# Manas_JLCPCB_2020-11-11_10-35-08.net
KiCad netlist of a schematic drawn in EasyEDA
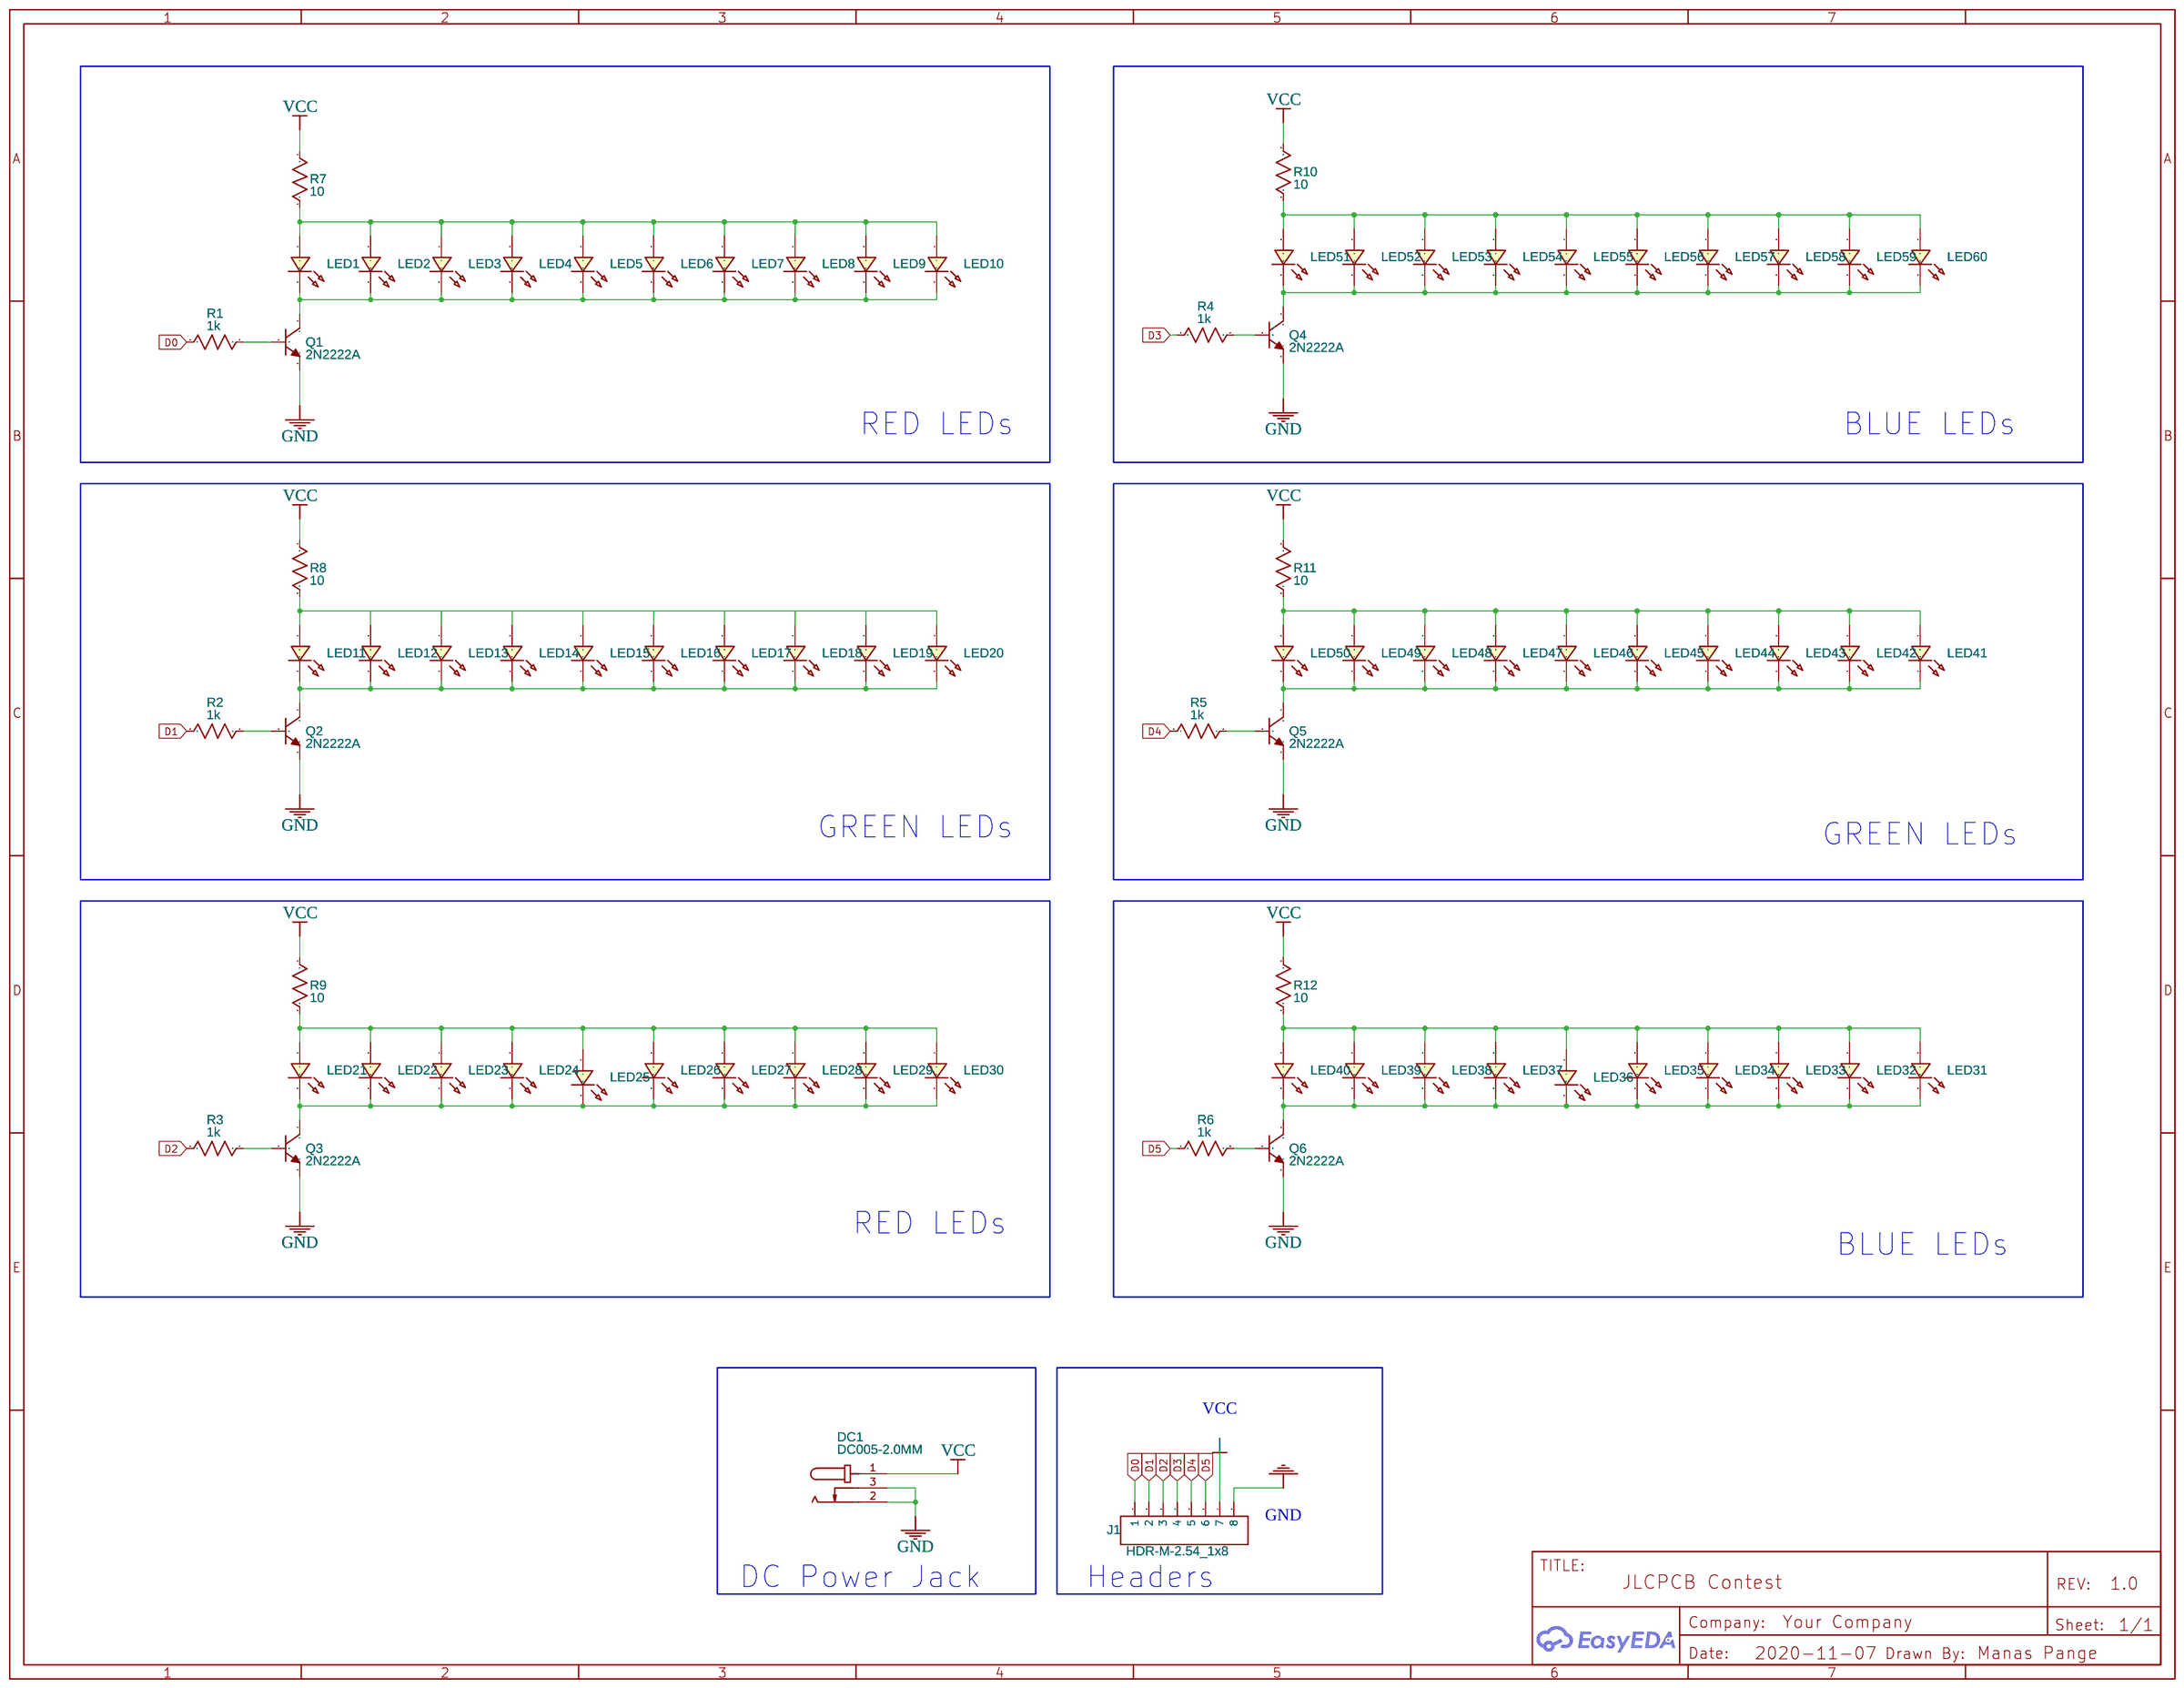
[diagram p0: schematic sheet]

(export (version "E")
  (design (tool "Eeschema 10.0.6"))
  (components
    (comp (ref "DC1")
      (value "DC005-2.0MM")
      (fields (field (name "BOM_Supplier Part") "C111567"))
      (libsource (lib "") (part "DC005-2.0MM"))
    )
    (comp (ref "J1")
      (value "HDR-M-2.54_1x8")
      (fields (field (name "BOM_Supplier Part") "C190820"))
      (libsource (lib "") (part "HDR-M-2.54_1x8"))
    )
    (comp (ref "LED1")
      (value "LED-TH-3mm_R")
      (fields
        (field (name "BOM_Manufacturer Part") "204-10SDRD/S530-A3-L")
        (field (name "BOM_Supplier Part") "C84774")
      )
      (libsource (lib "") (part "LED-TH-3mm_R"))
    )
    (comp (ref "LED2")
      (value "LED-TH-3mm_R")
      (fields
        (field (name "BOM_Manufacturer Part") "204-10SDRD/S530-A3-L")
        (field (name "BOM_Supplier Part") "C84774")
      )
      (libsource (lib "") (part "LED-TH-3mm_R"))
    )
    (comp (ref "LED3")
      (value "LED-TH-3mm_R")
      (fields
        (field (name "BOM_Manufacturer Part") "204-10SDRD/S530-A3-L")
        (field (name "BOM_Supplier Part") "C84774")
      )
      (libsource (lib "") (part "LED-TH-3mm_R"))
    )
    (comp (ref "LED4")
      (value "LED-TH-3mm_R")
      (fields
        (field (name "BOM_Manufacturer Part") "204-10SDRD/S530-A3-L")
        (field (name "BOM_Supplier Part") "C84774")
      )
      (libsource (lib "") (part "LED-TH-3mm_R"))
    )
    (comp (ref "LED5")
      (value "LED-TH-3mm_R")
      (fields
        (field (name "BOM_Manufacturer Part") "204-10SDRD/S530-A3-L")
        (field (name "BOM_Supplier Part") "C84774")
      )
      (libsource (lib "") (part "LED-TH-3mm_R"))
    )
    (comp (ref "LED6")
      (value "LED-TH-3mm_R")
      (fields
        (field (name "BOM_Manufacturer Part") "204-10SDRD/S530-A3-L")
        (field (name "BOM_Supplier Part") "C84774")
      )
      (libsource (lib "") (part "LED-TH-3mm_R"))
    )
    (comp (ref "LED7")
      (value "LED-TH-3mm_R")
      (fields
        (field (name "BOM_Manufacturer Part") "204-10SDRD/S530-A3-L")
        (field (name "BOM_Supplier Part") "C84774")
      )
      (libsource (lib "") (part "LED-TH-3mm_R"))
    )
    (comp (ref "LED8")
      (value "LED-TH-3mm_R")
      (fields
        (field (name "BOM_Manufacturer Part") "204-10SDRD/S530-A3-L")
        (field (name "BOM_Supplier Part") "C84774")
      )
      (libsource (lib "") (part "LED-TH-3mm_R"))
    )
    (comp (ref "LED9")
      (value "LED-TH-3mm_R")
      (fields
        (field (name "BOM_Manufacturer Part") "204-10SDRD/S530-A3-L")
        (field (name "BOM_Supplier Part") "C84774")
      )
      (libsource (lib "") (part "LED-TH-3mm_R"))
    )
    (comp (ref "LED10")
      (value "LED-TH-3mm_R")
      (fields
        (field (name "BOM_Manufacturer Part") "204-10SDRD/S530-A3-L")
        (field (name "BOM_Supplier Part") "C84774")
      )
      (libsource (lib "") (part "LED-TH-3mm_R"))
    )
    (comp (ref "LED11")
      (value "LED-TH-3mm_G")
      (fields
        (field (name "BOM_Manufacturer Part") "204-10SYGD/S530-E3")
        (field (name "BOM_Supplier Part") "C85161")
      )
      (libsource (lib "") (part "LED-TH-3mm_G"))
    )
    (comp (ref "LED12")
      (value "LED-TH-3mm_G")
      (fields
        (field (name "BOM_Manufacturer Part") "204-10SYGD/S530-E3")
        (field (name "BOM_Supplier Part") "C85161")
      )
      (libsource (lib "") (part "LED-TH-3mm_G"))
    )
    (comp (ref "LED13")
      (value "LED-TH-3mm_G")
      (fields
        (field (name "BOM_Manufacturer Part") "204-10SYGD/S530-E3")
        (field (name "BOM_Supplier Part") "C85161")
      )
      (libsource (lib "") (part "LED-TH-3mm_G"))
    )
    (comp (ref "LED14")
      (value "LED-TH-3mm_G")
      (fields
        (field (name "BOM_Manufacturer Part") "204-10SYGD/S530-E3")
        (field (name "BOM_Supplier Part") "C85161")
      )
      (libsource (lib "") (part "LED-TH-3mm_G"))
    )
    (comp (ref "LED15")
      (value "LED-TH-3mm_G")
      (fields
        (field (name "BOM_Manufacturer Part") "204-10SYGD/S530-E3")
        (field (name "BOM_Supplier Part") "C85161")
      )
      (libsource (lib "") (part "LED-TH-3mm_G"))
    )
    (comp (ref "LED16")
      (value "LED-TH-3mm_G")
      (fields
        (field (name "BOM_Manufacturer Part") "204-10SYGD/S530-E3")
        (field (name "BOM_Supplier Part") "C85161")
      )
      (libsource (lib "") (part "LED-TH-3mm_G"))
    )
    (comp (ref "LED17")
      (value "LED-TH-3mm_G")
      (fields
        (field (name "BOM_Manufacturer Part") "204-10SYGD/S530-E3")
        (field (name "BOM_Supplier Part") "C85161")
      )
      (libsource (lib "") (part "LED-TH-3mm_G"))
    )
    (comp (ref "LED18")
      (value "LED-TH-3mm_G")
      (fields
        (field (name "BOM_Manufacturer Part") "204-10SYGD/S530-E3")
        (field (name "BOM_Supplier Part") "C85161")
      )
      (libsource (lib "") (part "LED-TH-3mm_G"))
    )
    (comp (ref "LED19")
      (value "LED-TH-3mm_G")
      (fields
        (field (name "BOM_Manufacturer Part") "204-10SYGD/S530-E3")
        (field (name "BOM_Supplier Part") "C85161")
      )
      (libsource (lib "") (part "LED-TH-3mm_G"))
    )
    (comp (ref "LED20")
      (value "LED-TH-3mm_G")
      (fields
        (field (name "BOM_Manufacturer Part") "204-10SYGD/S530-E3")
        (field (name "BOM_Supplier Part") "C85161")
      )
      (libsource (lib "") (part "LED-TH-3mm_G"))
    )
    (comp (ref "LED21")
      (value "LED-TH-3mm_R")
      (fields
        (field (name "BOM_Manufacturer Part") "204-10SDRD/S530-A3-L")
        (field (name "BOM_Supplier Part") "C84774")
      )
      (libsource (lib "") (part "LED-TH-3mm_R"))
    )
    (comp (ref "LED22")
      (value "LED-TH-3mm_R")
      (fields
        (field (name "BOM_Manufacturer Part") "204-10SDRD/S530-A3-L")
        (field (name "BOM_Supplier Part") "C84774")
      )
      (libsource (lib "") (part "LED-TH-3mm_R"))
    )
    (comp (ref "LED23")
      (value "LED-TH-3mm_R")
      (fields
        (field (name "BOM_Manufacturer Part") "204-10SDRD/S530-A3-L")
        (field (name "BOM_Supplier Part") "C84774")
      )
      (libsource (lib "") (part "LED-TH-3mm_R"))
    )
    (comp (ref "LED24")
      (value "LED-TH-3mm_R")
      (fields
        (field (name "BOM_Manufacturer Part") "204-10SDRD/S530-A3-L")
        (field (name "BOM_Supplier Part") "C84774")
      )
      (libsource (lib "") (part "LED-TH-3mm_R"))
    )
    (comp (ref "LED25")
      (value "LED-TH-3mm_R")
      (fields
        (field (name "BOM_Manufacturer Part") "204-10SDRD/S530-A3-L")
        (field (name "BOM_Supplier Part") "C84774")
      )
      (libsource (lib "") (part "LED-TH-3mm_R"))
    )
    (comp (ref "LED26")
      (value "LED-TH-3mm_R")
      (fields
        (field (name "BOM_Manufacturer Part") "204-10SDRD/S530-A3-L")
        (field (name "BOM_Supplier Part") "C84774")
      )
      (libsource (lib "") (part "LED-TH-3mm_R"))
    )
    (comp (ref "LED27")
      (value "LED-TH-3mm_R")
      (fields
        (field (name "BOM_Manufacturer Part") "204-10SDRD/S530-A3-L")
        (field (name "BOM_Supplier Part") "C84774")
      )
      (libsource (lib "") (part "LED-TH-3mm_R"))
    )
    (comp (ref "LED28")
      (value "LED-TH-3mm_R")
      (fields
        (field (name "BOM_Manufacturer Part") "204-10SDRD/S530-A3-L")
        (field (name "BOM_Supplier Part") "C84774")
      )
      (libsource (lib "") (part "LED-TH-3mm_R"))
    )
    (comp (ref "LED29")
      (value "LED-TH-3mm_R")
      (fields
        (field (name "BOM_Manufacturer Part") "204-10SDRD/S530-A3-L")
        (field (name "BOM_Supplier Part") "C84774")
      )
      (libsource (lib "") (part "LED-TH-3mm_R"))
    )
    (comp (ref "LED30")
      (value "LED-TH-3mm_R")
      (fields
        (field (name "BOM_Manufacturer Part") "204-10SDRD/S530-A3-L")
        (field (name "BOM_Supplier Part") "C84774")
      )
      (libsource (lib "") (part "LED-TH-3mm_R"))
    )
    (comp (ref "LED31")
      (value "LED-TH-3mm_B")
      (fields
        (field (name "BOM_Manufacturer Part") "204-10SUBC/S400-A4")
        (field (name "BOM_Supplier Part") "C86881")
      )
      (libsource (lib "") (part "LED-TH-3mm_B"))
    )
    (comp (ref "LED32")
      (value "LED-TH-3mm_B")
      (fields
        (field (name "BOM_Manufacturer Part") "204-10SUBC/S400-A4")
        (field (name "BOM_Supplier Part") "C86881")
      )
      (libsource (lib "") (part "LED-TH-3mm_B"))
    )
    (comp (ref "LED33")
      (value "LED-TH-3mm_B")
      (fields
        (field (name "BOM_Manufacturer Part") "204-10SUBC/S400-A4")
        (field (name "BOM_Supplier Part") "C86881")
      )
      (libsource (lib "") (part "LED-TH-3mm_B"))
    )
    (comp (ref "LED34")
      (value "LED-TH-3mm_B")
      (fields
        (field (name "BOM_Manufacturer Part") "204-10SUBC/S400-A4")
        (field (name "BOM_Supplier Part") "C86881")
      )
      (libsource (lib "") (part "LED-TH-3mm_B"))
    )
    (comp (ref "LED35")
      (value "LED-TH-3mm_B")
      (fields
        (field (name "BOM_Manufacturer Part") "204-10SUBC/S400-A4")
        (field (name "BOM_Supplier Part") "C86881")
      )
      (libsource (lib "") (part "LED-TH-3mm_B"))
    )
    (comp (ref "LED36")
      (value "LED-TH-3mm_B")
      (fields
        (field (name "BOM_Manufacturer Part") "204-10SUBC/S400-A4")
        (field (name "BOM_Supplier Part") "C86881")
      )
      (libsource (lib "") (part "LED-TH-3mm_B"))
    )
    (comp (ref "LED37")
      (value "LED-TH-3mm_B")
      (fields
        (field (name "BOM_Manufacturer Part") "204-10SUBC/S400-A4")
        (field (name "BOM_Supplier Part") "C86881")
      )
      (libsource (lib "") (part "LED-TH-3mm_B"))
    )
    (comp (ref "LED38")
      (value "LED-TH-3mm_B")
      (fields
        (field (name "BOM_Manufacturer Part") "204-10SUBC/S400-A4")
        (field (name "BOM_Supplier Part") "C86881")
      )
      (libsource (lib "") (part "LED-TH-3mm_B"))
    )
    (comp (ref "LED39")
      (value "LED-TH-3mm_B")
      (fields
        (field (name "BOM_Manufacturer Part") "204-10SUBC/S400-A4")
        (field (name "BOM_Supplier Part") "C86881")
      )
      (libsource (lib "") (part "LED-TH-3mm_B"))
    )
    (comp (ref "LED40")
      (value "LED-TH-3mm_B")
      (fields
        (field (name "BOM_Manufacturer Part") "204-10SUBC/S400-A4")
        (field (name "BOM_Supplier Part") "C86881")
      )
      (libsource (lib "") (part "LED-TH-3mm_B"))
    )
    (comp (ref "LED41")
      (value "LED-TH-3mm_G")
      (fields
        (field (name "BOM_Manufacturer Part") "204-10SYGD/S530-E3")
        (field (name "BOM_Supplier Part") "C85161")
      )
      (libsource (lib "") (part "LED-TH-3mm_G"))
    )
    (comp (ref "LED42")
      (value "LED-TH-3mm_G")
      (fields
        (field (name "BOM_Manufacturer Part") "204-10SYGD/S530-E3")
        (field (name "BOM_Supplier Part") "C85161")
      )
      (libsource (lib "") (part "LED-TH-3mm_G"))
    )
    (comp (ref "LED43")
      (value "LED-TH-3mm_G")
      (fields
        (field (name "BOM_Manufacturer Part") "204-10SYGD/S530-E3")
        (field (name "BOM_Supplier Part") "C85161")
      )
      (libsource (lib "") (part "LED-TH-3mm_G"))
    )
    (comp (ref "LED44")
      (value "LED-TH-3mm_G")
      (fields
        (field (name "BOM_Manufacturer Part") "204-10SYGD/S530-E3")
        (field (name "BOM_Supplier Part") "C85161")
      )
      (libsource (lib "") (part "LED-TH-3mm_G"))
    )
    (comp (ref "LED45")
      (value "LED-TH-3mm_G")
      (fields
        (field (name "BOM_Manufacturer Part") "204-10SYGD/S530-E3")
        (field (name "BOM_Supplier Part") "C85161")
      )
      (libsource (lib "") (part "LED-TH-3mm_G"))
    )
    (comp (ref "LED46")
      (value "LED-TH-3mm_G")
      (fields
        (field (name "BOM_Manufacturer Part") "204-10SYGD/S530-E3")
        (field (name "BOM_Supplier Part") "C85161")
      )
      (libsource (lib "") (part "LED-TH-3mm_G"))
    )
    (comp (ref "LED47")
      (value "LED-TH-3mm_G")
      (fields
        (field (name "BOM_Manufacturer Part") "204-10SYGD/S530-E3")
        (field (name "BOM_Supplier Part") "C85161")
      )
      (libsource (lib "") (part "LED-TH-3mm_G"))
    )
    (comp (ref "LED48")
      (value "LED-TH-3mm_G")
      (fields
        (field (name "BOM_Manufacturer Part") "204-10SYGD/S530-E3")
        (field (name "BOM_Supplier Part") "C85161")
      )
      (libsource (lib "") (part "LED-TH-3mm_G"))
    )
    (comp (ref "LED49")
      (value "LED-TH-3mm_G")
      (fields
        (field (name "BOM_Manufacturer Part") "204-10SYGD/S530-E3")
        (field (name "BOM_Supplier Part") "C85161")
      )
      (libsource (lib "") (part "LED-TH-3mm_G"))
    )
    (comp (ref "LED50")
      (value "LED-TH-3mm_G")
      (fields
        (field (name "BOM_Manufacturer Part") "204-10SYGD/S530-E3")
        (field (name "BOM_Supplier Part") "C85161")
      )
      (libsource (lib "") (part "LED-TH-3mm_G"))
    )
    (comp (ref "LED51")
      (value "LED-TH-3mm_B")
      (fields
        (field (name "BOM_Manufacturer Part") "204-10SUBC/S400-A4")
        (field (name "BOM_Supplier Part") "C86881")
      )
      (libsource (lib "") (part "LED-TH-3mm_B"))
    )
    (comp (ref "LED52")
      (value "LED-TH-3mm_B")
      (fields
        (field (name "BOM_Manufacturer Part") "204-10SUBC/S400-A4")
        (field (name "BOM_Supplier Part") "C86881")
      )
      (libsource (lib "") (part "LED-TH-3mm_B"))
    )
    (comp (ref "LED53")
      (value "LED-TH-3mm_B")
      (fields
        (field (name "BOM_Manufacturer Part") "204-10SUBC/S400-A4")
        (field (name "BOM_Supplier Part") "C86881")
      )
      (libsource (lib "") (part "LED-TH-3mm_B"))
    )
    (comp (ref "LED54")
      (value "LED-TH-3mm_B")
      (fields
        (field (name "BOM_Manufacturer Part") "204-10SUBC/S400-A4")
        (field (name "BOM_Supplier Part") "C86881")
      )
      (libsource (lib "") (part "LED-TH-3mm_B"))
    )
    (comp (ref "LED55")
      (value "LED-TH-3mm_B")
      (fields
        (field (name "BOM_Manufacturer Part") "204-10SUBC/S400-A4")
        (field (name "BOM_Supplier Part") "C86881")
      )
      (libsource (lib "") (part "LED-TH-3mm_B"))
    )
    (comp (ref "LED56")
      (value "LED-TH-3mm_B")
      (fields
        (field (name "BOM_Manufacturer Part") "204-10SUBC/S400-A4")
        (field (name "BOM_Supplier Part") "C86881")
      )
      (libsource (lib "") (part "LED-TH-3mm_B"))
    )
    (comp (ref "LED57")
      (value "LED-TH-3mm_B")
      (fields
        (field (name "BOM_Manufacturer Part") "204-10SUBC/S400-A4")
        (field (name "BOM_Supplier Part") "C86881")
      )
      (libsource (lib "") (part "LED-TH-3mm_B"))
    )
    (comp (ref "LED58")
      (value "LED-TH-3mm_B")
      (fields
        (field (name "BOM_Manufacturer Part") "204-10SUBC/S400-A4")
        (field (name "BOM_Supplier Part") "C86881")
      )
      (libsource (lib "") (part "LED-TH-3mm_B"))
    )
    (comp (ref "LED59")
      (value "LED-TH-3mm_B")
      (fields
        (field (name "BOM_Manufacturer Part") "204-10SUBC/S400-A4")
        (field (name "BOM_Supplier Part") "C86881")
      )
      (libsource (lib "") (part "LED-TH-3mm_B"))
    )
    (comp (ref "LED60")
      (value "LED-TH-3mm_B")
      (fields
        (field (name "BOM_Manufacturer Part") "204-10SUBC/S400-A4")
        (field (name "BOM_Supplier Part") "C86881")
      )
      (libsource (lib "") (part "LED-TH-3mm_B"))
    )
    (comp (ref "Q1")
      (value "2N2222A")
      (fields (field (name "BOM_Supplier Part") "C358533"))
      (libsource (lib "") (part "2N2222A"))
    )
    (comp (ref "Q2")
      (value "2N2222A")
      (fields (field (name "BOM_Supplier Part") "C358533"))
      (libsource (lib "") (part "2N2222A"))
    )
    (comp (ref "Q3")
      (value "2N2222A")
      (fields (field (name "BOM_Supplier Part") "C358533"))
      (libsource (lib "") (part "2N2222A"))
    )
    (comp (ref "Q4")
      (value "2N2222A")
      (fields (field (name "BOM_Supplier Part") "C358533"))
      (libsource (lib "") (part "2N2222A"))
    )
    (comp (ref "Q5")
      (value "2N2222A")
      (fields (field (name "BOM_Supplier Part") "C358533"))
      (libsource (lib "") (part "2N2222A"))
    )
    (comp (ref "Q6")
      (value "2N2222A")
      (fields (field (name "BOM_Supplier Part") "C358533"))
      (libsource (lib "") (part "2N2222A"))
    )
    (comp (ref "R1") (value "1k") (libsource (lib "") (part "R_AXIAL-0.3_US")))
    (comp (ref "R2") (value "1k") (libsource (lib "") (part "R_AXIAL-0.3_US")))
    (comp (ref "R3") (value "1k") (libsource (lib "") (part "R_AXIAL-0.3_US")))
    (comp (ref "R4") (value "1k") (libsource (lib "") (part "R_AXIAL-0.3_US_1")))
    (comp (ref "R5") (value "1k") (libsource (lib "") (part "R_AXIAL-0.3_US")))
    (comp (ref "R6") (value "1k") (libsource (lib "") (part "R_AXIAL-0.3_US")))
    (comp (ref "R7") (value "10") (libsource (lib "") (part "R_AXIAL-0.5_US")))
    (comp (ref "R8") (value "10") (libsource (lib "") (part "R_AXIAL-0.5_US")))
    (comp (ref "R9") (value "10") (libsource (lib "") (part "R_AXIAL-0.5_US")))
    (comp (ref "R10") (value "10") (libsource (lib "") (part "R_AXIAL-0.5_US")))
    (comp (ref "R11") (value "10") (libsource (lib "") (part "R_AXIAL-0.5_US")))
    (comp (ref "R12") (value "10") (libsource (lib "") (part "R_AXIAL-0.5_US")))
  )
  (nets
    (net (code "1") (name "D0") (class "Default")
      (node (ref "R1") (pin "1") (pinfunction "1_1") (pintype "unspecified"))
    )
    (net (code "2") (name "D1") (class "Default")
      (node (ref "R2") (pin "1") (pinfunction "1_1") (pintype "unspecified"))
    )
    (net (code "3") (name "D2") (class "Default")
      (node (ref "R3") (pin "1") (pinfunction "1_1") (pintype "unspecified"))
    )
    (net (code "4") (name "D3") (class "Default")
      (node (ref "R4") (pin "2") (pinfunction "2_2") (pintype "unspecified"))
    )
    (net (code "5") (name "D4") (class "Default")
      (node (ref "R5") (pin "1") (pinfunction "1_1") (pintype "unspecified"))
    )
    (net (code "6") (name "D5") (class "Default")
      (node (ref "R6") (pin "1") (pinfunction "1_1") (pintype "unspecified"))
    )
    (net (code "7") (name "GND") (class "Default")
      (node (ref "DC1") (pin "2") (pinfunction "2_2") (pintype "unspecified"))
      (node (ref "DC1") (pin "3") (pinfunction "3_3") (pintype "unspecified"))
      (node (ref "Q1") (pin "3") (pinfunction "E_3") (pintype "unspecified"))
      (node (ref "Q2") (pin "3") (pinfunction "E_3") (pintype "unspecified"))
      (node (ref "Q3") (pin "3") (pinfunction "E_3") (pintype "unspecified"))
      (node (ref "Q4") (pin "3") (pinfunction "E_3") (pintype "unspecified"))
      (node (ref "Q5") (pin "3") (pinfunction "E_3") (pintype "unspecified"))
      (node (ref "Q6") (pin "3") (pinfunction "E_3") (pintype "unspecified"))
    )
    (net (code "8") (name "Net-(LED1-Pad1)") (class "Default")
      (node (ref "LED1") (pin "1") (pinfunction "1_1") (pintype "unspecified"))
      (node (ref "LED10") (pin "1") (pinfunction "1_1") (pintype "unspecified"))
      (node (ref "LED2") (pin "1") (pinfunction "1_1") (pintype "unspecified"))
      (node (ref "LED3") (pin "1") (pinfunction "1_1") (pintype "unspecified"))
      (node (ref "LED4") (pin "1") (pinfunction "1_1") (pintype "unspecified"))
      (node (ref "LED5") (pin "1") (pinfunction "1_1") (pintype "unspecified"))
      (node (ref "LED6") (pin "1") (pinfunction "1_1") (pintype "unspecified"))
      (node (ref "LED7") (pin "1") (pinfunction "1_1") (pintype "unspecified"))
      (node (ref "LED8") (pin "1") (pinfunction "1_1") (pintype "unspecified"))
      (node (ref "LED9") (pin "1") (pinfunction "1_1") (pintype "unspecified"))
      (node (ref "R7") (pin "2") (pinfunction "2_2") (pintype "unspecified"))
    )
    (net (code "9") (name "Net-(LED11-Pad1)") (class "Default")
      (node (ref "LED11") (pin "1") (pinfunction "1_1") (pintype "unspecified"))
      (node (ref "LED20") (pin "1") (pinfunction "1_1") (pintype "unspecified"))
      (node (ref "R8") (pin "2") (pinfunction "2_2") (pintype "unspecified"))
    )
    (net (code "10") (name "Net-(LED21-Pad1)") (class "Default")
      (node (ref "LED21") (pin "1") (pinfunction "1_1") (pintype "unspecified"))
      (node (ref "LED22") (pin "1") (pinfunction "1_1") (pintype "unspecified"))
      (node (ref "LED23") (pin "1") (pinfunction "1_1") (pintype "unspecified"))
      (node (ref "LED24") (pin "1") (pinfunction "1_1") (pintype "unspecified"))
      (node (ref "LED25") (pin "1") (pinfunction "1_1") (pintype "unspecified"))
      (node (ref "LED26") (pin "1") (pinfunction "1_1") (pintype "unspecified"))
      (node (ref "LED27") (pin "1") (pinfunction "1_1") (pintype "unspecified"))
      (node (ref "LED28") (pin "1") (pinfunction "1_1") (pintype "unspecified"))
      (node (ref "LED29") (pin "1") (pinfunction "1_1") (pintype "unspecified"))
      (node (ref "LED30") (pin "1") (pinfunction "1_1") (pintype "unspecified"))
      (node (ref "R9") (pin "2") (pinfunction "2_2") (pintype "unspecified"))
    )
    (net (code "11") (name "Net-(LED31-Pad1)") (class "Default")
      (node (ref "LED31") (pin "1") (pinfunction "1_1") (pintype "unspecified"))
      (node (ref "LED32") (pin "1") (pinfunction "1_1") (pintype "unspecified"))
      (node (ref "LED33") (pin "1") (pinfunction "1_1") (pintype "unspecified"))
      (node (ref "LED34") (pin "1") (pinfunction "1_1") (pintype "unspecified"))
      (node (ref "LED35") (pin "1") (pinfunction "1_1") (pintype "unspecified"))
      (node (ref "LED36") (pin "1") (pinfunction "1_1") (pintype "unspecified"))
      (node (ref "LED37") (pin "1") (pinfunction "1_1") (pintype "unspecified"))
      (node (ref "LED38") (pin "1") (pinfunction "1_1") (pintype "unspecified"))
      (node (ref "LED39") (pin "1") (pinfunction "1_1") (pintype "unspecified"))
      (node (ref "LED40") (pin "1") (pinfunction "1_1") (pintype "unspecified"))
      (node (ref "R12") (pin "2") (pinfunction "2_2") (pintype "unspecified"))
    )
    (net (code "12") (name "Net-(LED41-Pad1)") (class "Default")
      (node (ref "LED41") (pin "1") (pinfunction "1_1") (pintype "unspecified"))
      (node (ref "LED42") (pin "1") (pinfunction "1_1") (pintype "unspecified"))
      (node (ref "LED43") (pin "1") (pinfunction "1_1") (pintype "unspecified"))
      (node (ref "LED44") (pin "1") (pinfunction "1_1") (pintype "unspecified"))
      (node (ref "LED45") (pin "1") (pinfunction "1_1") (pintype "unspecified"))
      (node (ref "LED46") (pin "1") (pinfunction "1_1") (pintype "unspecified"))
      (node (ref "LED47") (pin "1") (pinfunction "1_1") (pintype "unspecified"))
      (node (ref "LED48") (pin "1") (pinfunction "1_1") (pintype "unspecified"))
      (node (ref "LED49") (pin "1") (pinfunction "1_1") (pintype "unspecified"))
      (node (ref "LED50") (pin "1") (pinfunction "1_1") (pintype "unspecified"))
      (node (ref "R11") (pin "2") (pinfunction "2_2") (pintype "unspecified"))
    )
    (net (code "13") (name "Net-(LED51-Pad1)") (class "Default")
      (node (ref "LED51") (pin "1") (pinfunction "1_1") (pintype "unspecified"))
      (node (ref "LED52") (pin "1") (pinfunction "1_1") (pintype "unspecified"))
      (node (ref "LED53") (pin "1") (pinfunction "1_1") (pintype "unspecified"))
      (node (ref "LED54") (pin "1") (pinfunction "1_1") (pintype "unspecified"))
      (node (ref "LED55") (pin "1") (pinfunction "1_1") (pintype "unspecified"))
      (node (ref "LED56") (pin "1") (pinfunction "1_1") (pintype "unspecified"))
      (node (ref "LED57") (pin "1") (pinfunction "1_1") (pintype "unspecified"))
      (node (ref "LED58") (pin "1") (pinfunction "1_1") (pintype "unspecified"))
      (node (ref "LED59") (pin "1") (pinfunction "1_1") (pintype "unspecified"))
      (node (ref "LED60") (pin "1") (pinfunction "1_1") (pintype "unspecified"))
      (node (ref "R10") (pin "2") (pinfunction "2_2") (pintype "unspecified"))
    )
    (net (code "14") (name "Net-(Q1-B)") (class "Default")
      (node (ref "Q1") (pin "2") (pinfunction "B_2") (pintype "unspecified"))
      (node (ref "R1") (pin "2") (pinfunction "2_2") (pintype "unspecified"))
    )
    (net (code "15") (name "Net-(Q1-C)") (class "Default")
      (node (ref "LED1") (pin "2") (pinfunction "2_2") (pintype "unspecified"))
      (node (ref "LED10") (pin "2") (pinfunction "2_2") (pintype "unspecified"))
      (node (ref "LED2") (pin "2") (pinfunction "2_2") (pintype "unspecified"))
      (node (ref "LED3") (pin "2") (pinfunction "2_2") (pintype "unspecified"))
      (node (ref "LED4") (pin "2") (pinfunction "2_2") (pintype "unspecified"))
      (node (ref "LED5") (pin "2") (pinfunction "2_2") (pintype "unspecified"))
      (node (ref "LED6") (pin "2") (pinfunction "2_2") (pintype "unspecified"))
      (node (ref "LED7") (pin "2") (pinfunction "2_2") (pintype "unspecified"))
      (node (ref "LED8") (pin "2") (pinfunction "2_2") (pintype "unspecified"))
      (node (ref "LED9") (pin "2") (pinfunction "2_2") (pintype "unspecified"))
      (node (ref "Q1") (pin "1") (pinfunction "C_1") (pintype "unspecified"))
    )
    (net (code "16") (name "Net-(Q2-B)") (class "Default")
      (node (ref "Q2") (pin "2") (pinfunction "B_2") (pintype "unspecified"))
      (node (ref "R2") (pin "2") (pinfunction "2_2") (pintype "unspecified"))
    )
    (net (code "17") (name "Net-(Q2-C)") (class "Default")
      (node (ref "LED11") (pin "2") (pinfunction "2_2") (pintype "unspecified"))
      (node (ref "LED12") (pin "2") (pinfunction "2_2") (pintype "unspecified"))
      (node (ref "LED13") (pin "2") (pinfunction "2_2") (pintype "unspecified"))
      (node (ref "LED14") (pin "2") (pinfunction "2_2") (pintype "unspecified"))
      (node (ref "LED15") (pin "2") (pinfunction "2_2") (pintype "unspecified"))
      (node (ref "LED16") (pin "2") (pinfunction "2_2") (pintype "unspecified"))
      (node (ref "LED17") (pin "2") (pinfunction "2_2") (pintype "unspecified"))
      (node (ref "LED18") (pin "2") (pinfunction "2_2") (pintype "unspecified"))
      (node (ref "LED19") (pin "2") (pinfunction "2_2") (pintype "unspecified"))
      (node (ref "LED20") (pin "2") (pinfunction "2_2") (pintype "unspecified"))
      (node (ref "Q2") (pin "1") (pinfunction "C_1") (pintype "unspecified"))
    )
    (net (code "18") (name "Net-(Q3-B)") (class "Default")
      (node (ref "Q3") (pin "2") (pinfunction "B_2") (pintype "unspecified"))
      (node (ref "R3") (pin "2") (pinfunction "2_2") (pintype "unspecified"))
    )
    (net (code "19") (name "Net-(Q3-C)") (class "Default")
      (node (ref "LED21") (pin "2") (pinfunction "2_2") (pintype "unspecified"))
      (node (ref "LED22") (pin "2") (pinfunction "2_2") (pintype "unspecified"))
      (node (ref "LED23") (pin "2") (pinfunction "2_2") (pintype "unspecified"))
      (node (ref "LED24") (pin "2") (pinfunction "2_2") (pintype "unspecified"))
      (node (ref "LED25") (pin "2") (pinfunction "2_2") (pintype "unspecified"))
      (node (ref "LED26") (pin "2") (pinfunction "2_2") (pintype "unspecified"))
      (node (ref "LED27") (pin "2") (pinfunction "2_2") (pintype "unspecified"))
      (node (ref "LED28") (pin "2") (pinfunction "2_2") (pintype "unspecified"))
      (node (ref "LED29") (pin "2") (pinfunction "2_2") (pintype "unspecified"))
      (node (ref "LED30") (pin "2") (pinfunction "2_2") (pintype "unspecified"))
      (node (ref "Q3") (pin "1") (pinfunction "C_1") (pintype "unspecified"))
    )
    (net (code "20") (name "Net-(Q4-B)") (class "Default")
      (node (ref "Q4") (pin "2") (pinfunction "B_2") (pintype "unspecified"))
      (node (ref "R4") (pin "1") (pinfunction "1_1") (pintype "unspecified"))
    )
    (net (code "21") (name "Net-(Q4-C)") (class "Default")
      (node (ref "LED51") (pin "2") (pinfunction "2_2") (pintype "unspecified"))
      (node (ref "LED52") (pin "2") (pinfunction "2_2") (pintype "unspecified"))
      (node (ref "LED53") (pin "2") (pinfunction "2_2") (pintype "unspecified"))
      (node (ref "LED54") (pin "2") (pinfunction "2_2") (pintype "unspecified"))
      (node (ref "LED55") (pin "2") (pinfunction "2_2") (pintype "unspecified"))
      (node (ref "LED56") (pin "2") (pinfunction "2_2") (pintype "unspecified"))
      (node (ref "LED57") (pin "2") (pinfunction "2_2") (pintype "unspecified"))
      (node (ref "LED58") (pin "2") (pinfunction "2_2") (pintype "unspecified"))
      (node (ref "LED59") (pin "2") (pinfunction "2_2") (pintype "unspecified"))
      (node (ref "LED60") (pin "2") (pinfunction "2_2") (pintype "unspecified"))
      (node (ref "Q4") (pin "1") (pinfunction "C_1") (pintype "unspecified"))
    )
    (net (code "22") (name "Net-(Q5-B)") (class "Default")
      (node (ref "Q5") (pin "2") (pinfunction "B_2") (pintype "unspecified"))
      (node (ref "R5") (pin "2") (pinfunction "2_2") (pintype "unspecified"))
    )
    (net (code "23") (name "Net-(Q5-C)") (class "Default")
      (node (ref "LED41") (pin "2") (pinfunction "2_2") (pintype "unspecified"))
      (node (ref "LED42") (pin "2") (pinfunction "2_2") (pintype "unspecified"))
      (node (ref "LED43") (pin "2") (pinfunction "2_2") (pintype "unspecified"))
      (node (ref "LED44") (pin "2") (pinfunction "2_2") (pintype "unspecified"))
      (node (ref "LED45") (pin "2") (pinfunction "2_2") (pintype "unspecified"))
      (node (ref "LED46") (pin "2") (pinfunction "2_2") (pintype "unspecified"))
      (node (ref "LED47") (pin "2") (pinfunction "2_2") (pintype "unspecified"))
      (node (ref "LED48") (pin "2") (pinfunction "2_2") (pintype "unspecified"))
      (node (ref "LED49") (pin "2") (pinfunction "2_2") (pintype "unspecified"))
      (node (ref "LED50") (pin "2") (pinfunction "2_2") (pintype "unspecified"))
      (node (ref "Q5") (pin "1") (pinfunction "C_1") (pintype "unspecified"))
    )
    (net (code "24") (name "Net-(Q6-B)") (class "Default")
      (node (ref "Q6") (pin "2") (pinfunction "B_2") (pintype "unspecified"))
      (node (ref "R6") (pin "2") (pinfunction "2_2") (pintype "unspecified"))
    )
    (net (code "25") (name "Net-(Q6-C)") (class "Default")
      (node (ref "LED31") (pin "2") (pinfunction "2_2") (pintype "unspecified"))
      (node (ref "LED32") (pin "2") (pinfunction "2_2") (pintype "unspecified"))
      (node (ref "LED33") (pin "2") (pinfunction "2_2") (pintype "unspecified"))
      (node (ref "LED34") (pin "2") (pinfunction "2_2") (pintype "unspecified"))
      (node (ref "LED35") (pin "2") (pinfunction "2_2") (pintype "unspecified"))
      (node (ref "LED36") (pin "2") (pinfunction "2_2") (pintype "unspecified"))
      (node (ref "LED37") (pin "2") (pinfunction "2_2") (pintype "unspecified"))
      (node (ref "LED38") (pin "2") (pinfunction "2_2") (pintype "unspecified"))
      (node (ref "LED39") (pin "2") (pinfunction "2_2") (pintype "unspecified"))
      (node (ref "LED40") (pin "2") (pinfunction "2_2") (pintype "unspecified"))
      (node (ref "Q6") (pin "1") (pinfunction "C_1") (pintype "unspecified"))
    )
    (net (code "26") (name "VCC") (class "Default")
      (node (ref "DC1") (pin "1") (pinfunction "1_1") (pintype "unspecified"))
      (node (ref "J1") (pin "7") (pinfunction "7_7") (pintype "unspecified"))
      (node (ref "R10") (pin "1") (pinfunction "1_1") (pintype "unspecified"))
      (node (ref "R11") (pin "1") (pinfunction "1_1") (pintype "unspecified"))
      (node (ref "R12") (pin "1") (pinfunction "1_1") (pintype "unspecified"))
      (node (ref "R7") (pin "1") (pinfunction "1_1") (pintype "unspecified"))
      (node (ref "R8") (pin "1") (pinfunction "1_1") (pintype "unspecified"))
      (node (ref "R9") (pin "1") (pinfunction "1_1") (pintype "unspecified"))
    )
    (net (code "27") (name "unconnected-(J1-Pad1)") (class "Default")
      (node (ref "J1") (pin "1") (pinfunction "1_1") (pintype "unspecified"))
    )
    (net (code "28") (name "unconnected-(J1-Pad2)") (class "Default")
      (node (ref "J1") (pin "2") (pinfunction "2_2") (pintype "unspecified"))
    )
    (net (code "29") (name "unconnected-(J1-Pad3)") (class "Default")
      (node (ref "J1") (pin "3") (pinfunction "3_3") (pintype "unspecified"))
    )
    (net (code "30") (name "unconnected-(J1-Pad4)") (class "Default")
      (node (ref "J1") (pin "4") (pinfunction "4_4") (pintype "unspecified"))
    )
    (net (code "31") (name "unconnected-(J1-Pad5)") (class "Default")
      (node (ref "J1") (pin "5") (pinfunction "5_5") (pintype "unspecified"))
    )
    (net (code "32") (name "unconnected-(J1-Pad6)") (class "Default")
      (node (ref "J1") (pin "6") (pinfunction "6_6") (pintype "unspecified"))
    )
    (net (code "33") (name "unconnected-(J1-Pad8)") (class "Default")
      (node (ref "J1") (pin "8") (pinfunction "8_8") (pintype "unspecified"))
    )
    (net (code "34") (name "unconnected-(LED12-Pad1)") (class "Default")
      (node (ref "LED12") (pin "1") (pinfunction "1_1") (pintype "unspecified"))
    )
    (net (code "35") (name "unconnected-(LED13-Pad1)") (class "Default")
      (node (ref "LED13") (pin "1") (pinfunction "1_1") (pintype "unspecified"))
    )
    (net (code "36") (name "unconnected-(LED14-Pad1)") (class "Default")
      (node (ref "LED14") (pin "1") (pinfunction "1_1") (pintype "unspecified"))
    )
    (net (code "37") (name "unconnected-(LED15-Pad1)") (class "Default")
      (node (ref "LED15") (pin "1") (pinfunction "1_1") (pintype "unspecified"))
    )
    (net (code "38") (name "unconnected-(LED16-Pad1)") (class "Default")
      (node (ref "LED16") (pin "1") (pinfunction "1_1") (pintype "unspecified"))
    )
    (net (code "39") (name "unconnected-(LED17-Pad1)") (class "Default")
      (node (ref "LED17") (pin "1") (pinfunction "1_1") (pintype "unspecified"))
    )
    (net (code "40") (name "unconnected-(LED18-Pad1)") (class "Default")
      (node (ref "LED18") (pin "1") (pinfunction "1_1") (pintype "unspecified"))
    )
    (net (code "41") (name "unconnected-(LED19-Pad1)") (class "Default")
      (node (ref "LED19") (pin "1") (pinfunction "1_1") (pintype "unspecified"))
    )
  )
)
